# analog_in.net
KiCad netlist of a schematic drawn in Altium Designer
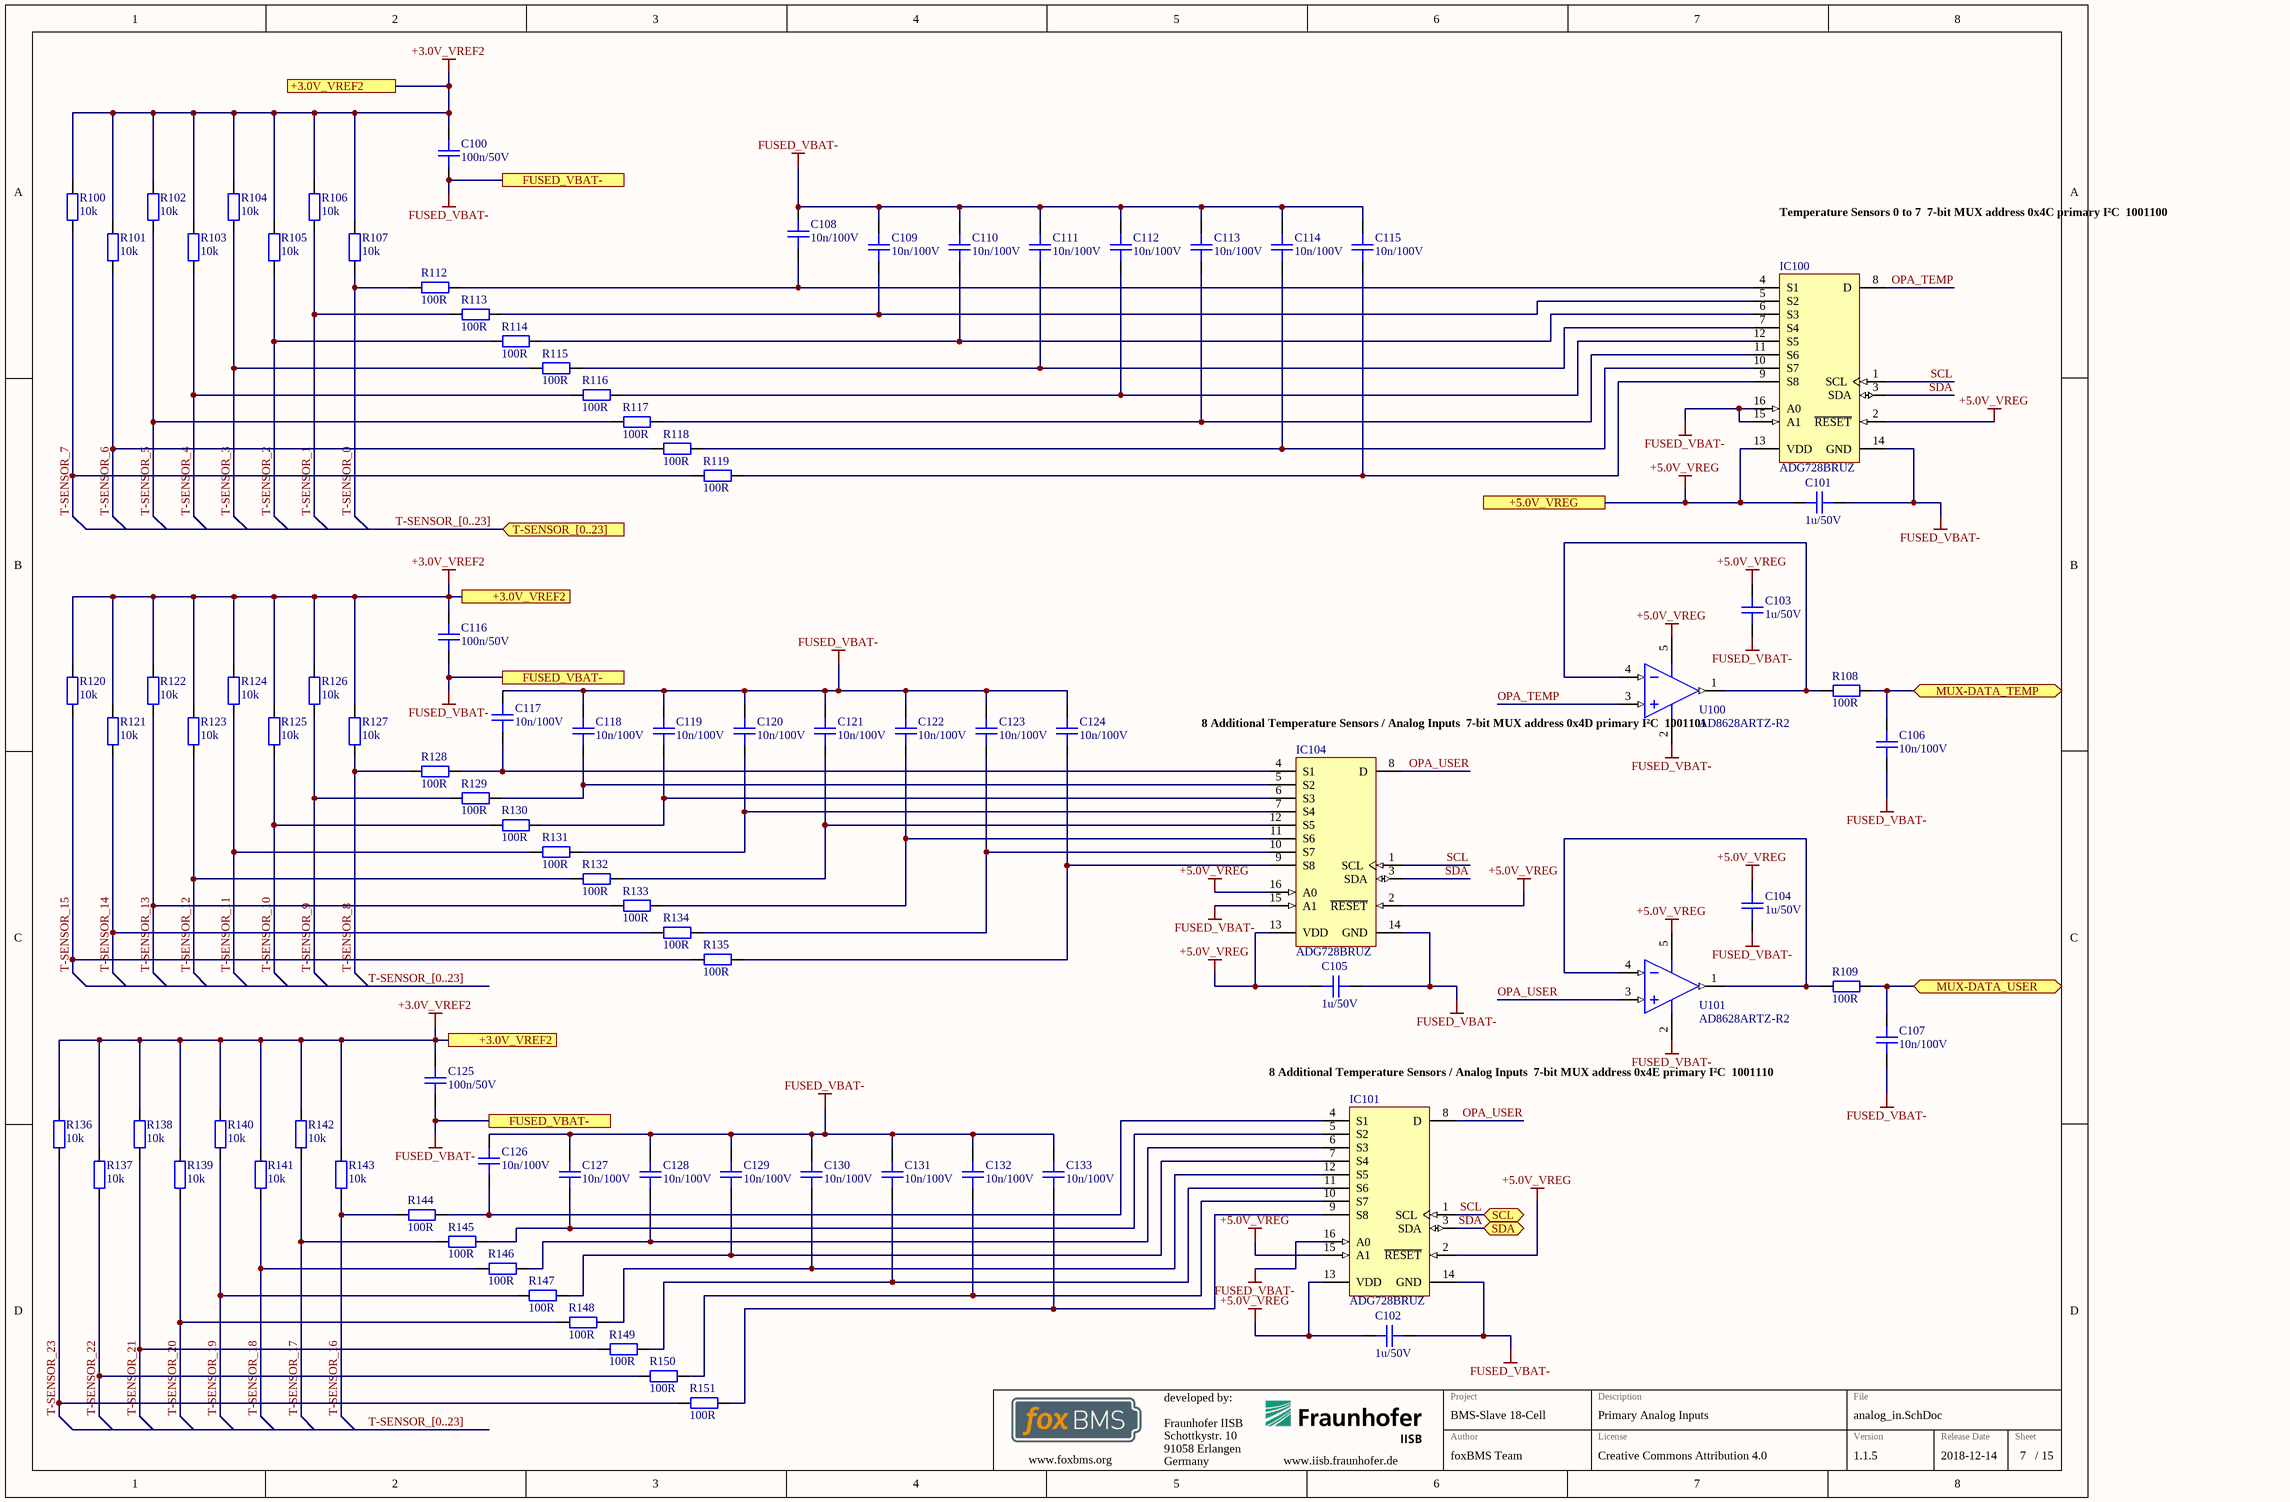
[diagram p0: analog_in.SchDoc]

(export (version "E")
  (design (tool "Eeschema 10.0.6"))
  (components
    (comp (ref "C100")
      (value "100n/50V")
      (footprint "CAPC1608X08N")
      (description "MLCC")
      (fields (field (name "PART NUMBER") "gen_C_ceramic_100n_50V_X7R_0603"))
      (libsource (lib "OE750") (part "C"))
    )
    (comp (ref "C101")
      (value "1u/50V")
      (footprint "CAPC2012X14N")
      (description "MLCC")
      (fields (field (name "PART NUMBER") "gen_C_ceramic_1u_50V_X7R_0805") (field (name "TOLERANCE") "± 10%"))
      (libsource (lib "OE750") (part "C"))
    )
    (comp (ref "C102")
      (value "1u/50V")
      (footprint "CAPC2012X14N")
      (description "MLCC")
      (fields (field (name "PART NUMBER") "gen_C_ceramic_1u_50V_X7R_0805") (field (name "TOLERANCE") "± 10%"))
      (libsource (lib "OE750") (part "C"))
    )
    (comp (ref "C103")
      (value "1u/50V")
      (footprint "CAPC2012X14N")
      (description "MLCC")
      (fields (field (name "PART NUMBER") "gen_C_ceramic_1u_50V_X7R_0805") (field (name "TOLERANCE") "± 10%"))
      (libsource (lib "OE750") (part "C"))
    )
    (comp (ref "C104")
      (value "1u/50V")
      (footprint "CAPC2012X14N")
      (description "MLCC")
      (fields (field (name "PART NUMBER") "gen_C_ceramic_1u_50V_X7R_0805") (field (name "TOLERANCE") "± 10%"))
      (libsource (lib "OE750") (part "C"))
    )
    (comp (ref "C105")
      (value "1u/50V")
      (footprint "CAPC2012X14N")
      (description "MLCC")
      (fields (field (name "PART NUMBER") "gen_C_ceramic_1u_50V_X7R_0805") (field (name "TOLERANCE") "± 10%"))
      (libsource (lib "OE750") (part "C"))
    )
    (comp (ref "C106")
      (value "10n/100V")
      (footprint "CAPC1608X08N")
      (description "MLCC")
      (fields (field (name "PART NUMBER") "gen_C_ceramic_10n_100V_X7R_0603"))
      (libsource (lib "OE750") (part "C"))
    )
    (comp (ref "C107")
      (value "10n/100V")
      (footprint "CAPC1608X08N")
      (description "MLCC")
      (fields (field (name "PART NUMBER") "gen_C_ceramic_10n_100V_X7R_0603"))
      (libsource (lib "OE750") (part "C"))
    )
    (comp (ref "C108")
      (value "10n/100V")
      (footprint "CAPC1608X08N")
      (description "MLCC")
      (fields (field (name "PART NUMBER") "gen_C_ceramic_10n_100V_X7R_0603"))
      (libsource (lib "OE750") (part "C"))
    )
    (comp (ref "C109")
      (value "10n/100V")
      (footprint "CAPC1608X08N")
      (description "MLCC")
      (fields (field (name "PART NUMBER") "gen_C_ceramic_10n_100V_X7R_0603"))
      (libsource (lib "OE750") (part "C"))
    )
    (comp (ref "C110")
      (value "10n/100V")
      (footprint "CAPC1608X08N")
      (description "MLCC")
      (fields (field (name "PART NUMBER") "gen_C_ceramic_10n_100V_X7R_0603"))
      (libsource (lib "OE750") (part "C"))
    )
    (comp (ref "C111")
      (value "10n/100V")
      (footprint "CAPC1608X08N")
      (description "MLCC")
      (fields (field (name "PART NUMBER") "gen_C_ceramic_10n_100V_X7R_0603"))
      (libsource (lib "OE750") (part "C"))
    )
    (comp (ref "C112")
      (value "10n/100V")
      (footprint "CAPC1608X08N")
      (description "MLCC")
      (fields (field (name "PART NUMBER") "gen_C_ceramic_10n_100V_X7R_0603"))
      (libsource (lib "OE750") (part "C"))
    )
    (comp (ref "C113")
      (value "10n/100V")
      (footprint "CAPC1608X08N")
      (description "MLCC")
      (fields (field (name "PART NUMBER") "gen_C_ceramic_10n_100V_X7R_0603"))
      (libsource (lib "OE750") (part "C"))
    )
    (comp (ref "C114")
      (value "10n/100V")
      (footprint "CAPC1608X08N")
      (description "MLCC")
      (fields (field (name "PART NUMBER") "gen_C_ceramic_10n_100V_X7R_0603"))
      (libsource (lib "OE750") (part "C"))
    )
    (comp (ref "C115")
      (value "10n/100V")
      (footprint "CAPC1608X08N")
      (description "MLCC")
      (fields (field (name "PART NUMBER") "gen_C_ceramic_10n_100V_X7R_0603"))
      (libsource (lib "OE750") (part "C"))
    )
    (comp (ref "C116")
      (value "100n/50V")
      (footprint "CAPC1608X08N")
      (description "MLCC")
      (fields (field (name "PART NUMBER") "gen_C_ceramic_100n_50V_X7R_0603"))
      (libsource (lib "OE750") (part "C"))
    )
    (comp (ref "C117")
      (value "10n/100V")
      (footprint "CAPC1608X08N")
      (description "MLCC")
      (fields (field (name "PART NUMBER") "gen_C_ceramic_10n_100V_X7R_0603"))
      (libsource (lib "OE750") (part "C"))
    )
    (comp (ref "C118")
      (value "10n/100V")
      (footprint "CAPC1608X08N")
      (description "MLCC")
      (fields (field (name "PART NUMBER") "gen_C_ceramic_10n_100V_X7R_0603"))
      (libsource (lib "OE750") (part "C"))
    )
    (comp (ref "C119")
      (value "10n/100V")
      (footprint "CAPC1608X08N")
      (description "MLCC")
      (fields (field (name "PART NUMBER") "gen_C_ceramic_10n_100V_X7R_0603"))
      (libsource (lib "OE750") (part "C"))
    )
    (comp (ref "C120")
      (value "10n/100V")
      (footprint "CAPC1608X08N")
      (description "MLCC")
      (fields (field (name "PART NUMBER") "gen_C_ceramic_10n_100V_X7R_0603"))
      (libsource (lib "OE750") (part "C"))
    )
    (comp (ref "C121")
      (value "10n/100V")
      (footprint "CAPC1608X08N")
      (description "MLCC")
      (fields (field (name "PART NUMBER") "gen_C_ceramic_10n_100V_X7R_0603"))
      (libsource (lib "OE750") (part "C"))
    )
    (comp (ref "C122")
      (value "10n/100V")
      (footprint "CAPC1608X08N")
      (description "MLCC")
      (fields (field (name "PART NUMBER") "gen_C_ceramic_10n_100V_X7R_0603"))
      (libsource (lib "OE750") (part "C"))
    )
    (comp (ref "C123")
      (value "10n/100V")
      (footprint "CAPC1608X08N")
      (description "MLCC")
      (fields (field (name "PART NUMBER") "gen_C_ceramic_10n_100V_X7R_0603"))
      (libsource (lib "OE750") (part "C"))
    )
    (comp (ref "C124")
      (value "10n/100V")
      (footprint "CAPC1608X08N")
      (description "MLCC")
      (fields (field (name "PART NUMBER") "gen_C_ceramic_10n_100V_X7R_0603"))
      (libsource (lib "OE750") (part "C"))
    )
    (comp (ref "C125")
      (value "100n/50V")
      (footprint "CAPC1608X08N")
      (description "MLCC")
      (fields (field (name "PART NUMBER") "gen_C_ceramic_100n_50V_X7R_0603"))
      (libsource (lib "OE750") (part "C"))
    )
    (comp (ref "C126")
      (value "10n/100V")
      (footprint "CAPC1608X08N")
      (description "MLCC")
      (fields (field (name "PART NUMBER") "gen_C_ceramic_10n_100V_X7R_0603"))
      (libsource (lib "OE750") (part "C"))
    )
    (comp (ref "C127")
      (value "10n/100V")
      (footprint "CAPC1608X08N")
      (description "MLCC")
      (fields (field (name "PART NUMBER") "gen_C_ceramic_10n_100V_X7R_0603"))
      (libsource (lib "OE750") (part "C"))
    )
    (comp (ref "C128")
      (value "10n/100V")
      (footprint "CAPC1608X08N")
      (description "MLCC")
      (fields (field (name "PART NUMBER") "gen_C_ceramic_10n_100V_X7R_0603"))
      (libsource (lib "OE750") (part "C"))
    )
    (comp (ref "C129")
      (value "10n/100V")
      (footprint "CAPC1608X08N")
      (description "MLCC")
      (fields (field (name "PART NUMBER") "gen_C_ceramic_10n_100V_X7R_0603"))
      (libsource (lib "OE750") (part "C"))
    )
    (comp (ref "C130")
      (value "10n/100V")
      (footprint "CAPC1608X08N")
      (description "MLCC")
      (fields (field (name "PART NUMBER") "gen_C_ceramic_10n_100V_X7R_0603"))
      (libsource (lib "OE750") (part "C"))
    )
    (comp (ref "C131")
      (value "10n/100V")
      (footprint "CAPC1608X08N")
      (description "MLCC")
      (fields (field (name "PART NUMBER") "gen_C_ceramic_10n_100V_X7R_0603"))
      (libsource (lib "OE750") (part "C"))
    )
    (comp (ref "C132")
      (value "10n/100V")
      (footprint "CAPC1608X08N")
      (description "MLCC")
      (fields (field (name "PART NUMBER") "gen_C_ceramic_10n_100V_X7R_0603"))
      (libsource (lib "OE750") (part "C"))
    )
    (comp (ref "C133")
      (value "10n/100V")
      (footprint "CAPC1608X08N")
      (description "MLCC")
      (fields (field (name "PART NUMBER") "gen_C_ceramic_10n_100V_X7R_0603"))
      (libsource (lib "OE750") (part "C"))
    )
    (comp (ref "IC100")
      (value "ADG728BRUZ")
      (footprint "ADI-RU-16_M")
      (fields (field (name "MANUFACTURER") "Analog Devices"))
      (libsource (lib "Altium Content Vault") (part "ADI-ADG728-RU-16"))
    )
    (comp (ref "IC101")
      (value "ADG728BRUZ")
      (footprint "ADI-RU-16_M")
      (fields (field (name "MANUFACTURER") "Analog Devices"))
      (libsource (lib "Altium Content Vault") (part "ADI-ADG728-RU-16"))
    )
    (comp (ref "IC104")
      (value "ADG728BRUZ")
      (footprint "ADI-RU-16_M")
      (fields (field (name "MANUFACTURER") "Analog Devices"))
      (libsource (lib "Altium Content Vault") (part "ADI-ADG728-RU-16"))
    )
    (comp (ref "R100")
      (value "10k")
      (footprint "RESC1608X05N")
      (description "SMD Resistor 10k 0603")
      (fields (field (name "PART NUMBER") "gen_R_10k_0603") (field (name "TOLERANCE") "1%"))
      (libsource (lib "OE750") (part "R"))
    )
    (comp (ref "R101")
      (value "10k")
      (footprint "RESC1608X05N")
      (description "SMD Resistor 10k 0603")
      (fields (field (name "PART NUMBER") "gen_R_10k_0603") (field (name "TOLERANCE") "1%"))
      (libsource (lib "OE750") (part "R"))
    )
    (comp (ref "R102")
      (value "10k")
      (footprint "RESC1608X05N")
      (description "SMD Resistor 10k 0603")
      (fields (field (name "PART NUMBER") "gen_R_10k_0603") (field (name "TOLERANCE") "1%"))
      (libsource (lib "OE750") (part "R"))
    )
    (comp (ref "R103")
      (value "10k")
      (footprint "RESC1608X05N")
      (description "SMD Resistor 10k 0603")
      (fields (field (name "PART NUMBER") "gen_R_10k_0603") (field (name "TOLERANCE") "1%"))
      (libsource (lib "OE750") (part "R"))
    )
    (comp (ref "R104")
      (value "10k")
      (footprint "RESC1608X05N")
      (description "SMD Resistor 10k 0603")
      (fields (field (name "PART NUMBER") "gen_R_10k_0603") (field (name "TOLERANCE") "1%"))
      (libsource (lib "OE750") (part "R"))
    )
    (comp (ref "R105")
      (value "10k")
      (footprint "RESC1608X05N")
      (description "SMD Resistor 10k 0603")
      (fields (field (name "PART NUMBER") "gen_R_10k_0603") (field (name "TOLERANCE") "1%"))
      (libsource (lib "OE750") (part "R"))
    )
    (comp (ref "R106")
      (value "10k")
      (footprint "RESC1608X05N")
      (description "SMD Resistor 10k 0603")
      (fields (field (name "PART NUMBER") "gen_R_10k_0603") (field (name "TOLERANCE") "1%"))
      (libsource (lib "OE750") (part "R"))
    )
    (comp (ref "R107")
      (value "10k")
      (footprint "RESC1608X05N")
      (description "SMD Resistor 10k 0603")
      (fields (field (name "PART NUMBER") "gen_R_10k_0603") (field (name "TOLERANCE") "1%"))
      (libsource (lib "OE750") (part "R"))
    )
    (comp (ref "R108")
      (value "100R")
      (footprint "RESC1608X05N")
      (description "SMD Resistor 100R 0603")
      (fields (field (name "PART NUMBER") "gen_R_100R_0603") (field (name "TOLERANCE") "1%"))
      (libsource (lib "OE750") (part "R"))
    )
    (comp (ref "R109")
      (value "100R")
      (footprint "RESC1608X05N")
      (description "SMD Resistor 100R 0603")
      (fields (field (name "PART NUMBER") "gen_R_100R_0603") (field (name "TOLERANCE") "1%"))
      (libsource (lib "OE750") (part "R"))
    )
    (comp (ref "R112")
      (value "100R")
      (footprint "RESC1608X05N")
      (description "SMD Resistor 100R 0603")
      (fields (field (name "PART NUMBER") "gen_R_100R_0603") (field (name "TOLERANCE") "1%"))
      (libsource (lib "OE750") (part "R"))
    )
    (comp (ref "R113")
      (value "100R")
      (footprint "RESC1608X05N")
      (description "SMD Resistor 100R 0603")
      (fields (field (name "PART NUMBER") "gen_R_100R_0603") (field (name "TOLERANCE") "1%"))
      (libsource (lib "OE750") (part "R"))
    )
    (comp (ref "R114")
      (value "100R")
      (footprint "RESC1608X05N")
      (description "SMD Resistor 100R 0603")
      (fields (field (name "PART NUMBER") "gen_R_100R_0603") (field (name "TOLERANCE") "1%"))
      (libsource (lib "OE750") (part "R"))
    )
    (comp (ref "R115")
      (value "100R")
      (footprint "RESC1608X05N")
      (description "SMD Resistor 100R 0603")
      (fields (field (name "PART NUMBER") "gen_R_100R_0603") (field (name "TOLERANCE") "1%"))
      (libsource (lib "OE750") (part "R"))
    )
    (comp (ref "R116")
      (value "100R")
      (footprint "RESC1608X05N")
      (description "SMD Resistor 100R 0603")
      (fields (field (name "PART NUMBER") "gen_R_100R_0603") (field (name "TOLERANCE") "1%"))
      (libsource (lib "OE750") (part "R"))
    )
    (comp (ref "R117")
      (value "100R")
      (footprint "RESC1608X05N")
      (description "SMD Resistor 100R 0603")
      (fields (field (name "PART NUMBER") "gen_R_100R_0603") (field (name "TOLERANCE") "1%"))
      (libsource (lib "OE750") (part "R"))
    )
    (comp (ref "R118")
      (value "100R")
      (footprint "RESC1608X05N")
      (description "SMD Resistor 100R 0603")
      (fields (field (name "PART NUMBER") "gen_R_100R_0603") (field (name "TOLERANCE") "1%"))
      (libsource (lib "OE750") (part "R"))
    )
    (comp (ref "R119")
      (value "100R")
      (footprint "RESC1608X05N")
      (description "SMD Resistor 100R 0603")
      (fields (field (name "PART NUMBER") "gen_R_100R_0603") (field (name "TOLERANCE") "1%"))
      (libsource (lib "OE750") (part "R"))
    )
    (comp (ref "R120")
      (value "10k")
      (footprint "RESC1608X05N")
      (description "SMD Resistor 10k 0603")
      (fields (field (name "PART NUMBER") "gen_R_10k_0603") (field (name "TOLERANCE") "1%"))
      (libsource (lib "OE750") (part "R"))
    )
    (comp (ref "R121")
      (value "10k")
      (footprint "RESC1608X05N")
      (description "SMD Resistor 10k 0603")
      (fields (field (name "PART NUMBER") "gen_R_10k_0603") (field (name "TOLERANCE") "1%"))
      (libsource (lib "OE750") (part "R"))
    )
    (comp (ref "R122")
      (value "10k")
      (footprint "RESC1608X05N")
      (description "SMD Resistor 10k 0603")
      (fields (field (name "PART NUMBER") "gen_R_10k_0603") (field (name "TOLERANCE") "1%"))
      (libsource (lib "OE750") (part "R"))
    )
    (comp (ref "R123")
      (value "10k")
      (footprint "RESC1608X05N")
      (description "SMD Resistor 10k 0603")
      (fields (field (name "PART NUMBER") "gen_R_10k_0603") (field (name "TOLERANCE") "1%"))
      (libsource (lib "OE750") (part "R"))
    )
    (comp (ref "R124")
      (value "10k")
      (footprint "RESC1608X05N")
      (description "SMD Resistor 10k 0603")
      (fields (field (name "PART NUMBER") "gen_R_10k_0603") (field (name "TOLERANCE") "1%"))
      (libsource (lib "OE750") (part "R"))
    )
    (comp (ref "R125")
      (value "10k")
      (footprint "RESC1608X05N")
      (description "SMD Resistor 10k 0603")
      (fields (field (name "PART NUMBER") "gen_R_10k_0603") (field (name "TOLERANCE") "1%"))
      (libsource (lib "OE750") (part "R"))
    )
    (comp (ref "R126")
      (value "10k")
      (footprint "RESC1608X05N")
      (description "SMD Resistor 10k 0603")
      (fields (field (name "PART NUMBER") "gen_R_10k_0603") (field (name "TOLERANCE") "1%"))
      (libsource (lib "OE750") (part "R"))
    )
    (comp (ref "R127")
      (value "10k")
      (footprint "RESC1608X05N")
      (description "SMD Resistor 10k 0603")
      (fields (field (name "PART NUMBER") "gen_R_10k_0603") (field (name "TOLERANCE") "1%"))
      (libsource (lib "OE750") (part "R"))
    )
    (comp (ref "R128")
      (value "100R")
      (footprint "RESC1608X05N")
      (description "SMD Resistor 100R 0603")
      (fields (field (name "PART NUMBER") "gen_R_100R_0603") (field (name "TOLERANCE") "1%"))
      (libsource (lib "OE750") (part "R"))
    )
    (comp (ref "R129")
      (value "100R")
      (footprint "RESC1608X05N")
      (description "SMD Resistor 100R 0603")
      (fields (field (name "PART NUMBER") "gen_R_100R_0603") (field (name "TOLERANCE") "1%"))
      (libsource (lib "OE750") (part "R"))
    )
    (comp (ref "R130")
      (value "100R")
      (footprint "RESC1608X05N")
      (description "SMD Resistor 100R 0603")
      (fields (field (name "PART NUMBER") "gen_R_100R_0603") (field (name "TOLERANCE") "1%"))
      (libsource (lib "OE750") (part "R"))
    )
    (comp (ref "R131")
      (value "100R")
      (footprint "RESC1608X05N")
      (description "SMD Resistor 100R 0603")
      (fields (field (name "PART NUMBER") "gen_R_100R_0603") (field (name "TOLERANCE") "1%"))
      (libsource (lib "OE750") (part "R"))
    )
    (comp (ref "R132")
      (value "100R")
      (footprint "RESC1608X05N")
      (description "SMD Resistor 100R 0603")
      (fields (field (name "PART NUMBER") "gen_R_100R_0603") (field (name "TOLERANCE") "1%"))
      (libsource (lib "OE750") (part "R"))
    )
    (comp (ref "R133")
      (value "100R")
      (footprint "RESC1608X05N")
      (description "SMD Resistor 100R 0603")
      (fields (field (name "PART NUMBER") "gen_R_100R_0603") (field (name "TOLERANCE") "1%"))
      (libsource (lib "OE750") (part "R"))
    )
    (comp (ref "R134")
      (value "100R")
      (footprint "RESC1608X05N")
      (description "SMD Resistor 100R 0603")
      (fields (field (name "PART NUMBER") "gen_R_100R_0603") (field (name "TOLERANCE") "1%"))
      (libsource (lib "OE750") (part "R"))
    )
    (comp (ref "R135")
      (value "100R")
      (footprint "RESC1608X05N")
      (description "SMD Resistor 100R 0603")
      (fields (field (name "PART NUMBER") "gen_R_100R_0603") (field (name "TOLERANCE") "1%"))
      (libsource (lib "OE750") (part "R"))
    )
    (comp (ref "R136")
      (value "10k")
      (footprint "RESC1608X05N")
      (description "SMD Resistor 10k 0603")
      (fields (field (name "PART NUMBER") "gen_R_10k_0603") (field (name "TOLERANCE") "1%"))
      (libsource (lib "OE750") (part "R"))
    )
    (comp (ref "R137")
      (value "10k")
      (footprint "RESC1608X05N")
      (description "SMD Resistor 10k 0603")
      (fields (field (name "PART NUMBER") "gen_R_10k_0603") (field (name "TOLERANCE") "1%"))
      (libsource (lib "OE750") (part "R"))
    )
    (comp (ref "R138")
      (value "10k")
      (footprint "RESC1608X05N")
      (description "SMD Resistor 10k 0603")
      (fields (field (name "PART NUMBER") "gen_R_10k_0603") (field (name "TOLERANCE") "1%"))
      (libsource (lib "OE750") (part "R"))
    )
    (comp (ref "R139")
      (value "10k")
      (footprint "RESC1608X05N")
      (description "SMD Resistor 10k 0603")
      (fields (field (name "PART NUMBER") "gen_R_10k_0603") (field (name "TOLERANCE") "1%"))
      (libsource (lib "OE750") (part "R"))
    )
    (comp (ref "R140")
      (value "10k")
      (footprint "RESC1608X05N")
      (description "SMD Resistor 10k 0603")
      (fields (field (name "PART NUMBER") "gen_R_10k_0603") (field (name "TOLERANCE") "1%"))
      (libsource (lib "OE750") (part "R"))
    )
    (comp (ref "R141")
      (value "10k")
      (footprint "RESC1608X05N")
      (description "SMD Resistor 10k 0603")
      (fields (field (name "PART NUMBER") "gen_R_10k_0603") (field (name "TOLERANCE") "1%"))
      (libsource (lib "OE750") (part "R"))
    )
    (comp (ref "R142")
      (value "10k")
      (footprint "RESC1608X05N")
      (description "SMD Resistor 10k 0603")
      (fields (field (name "PART NUMBER") "gen_R_10k_0603") (field (name "TOLERANCE") "1%"))
      (libsource (lib "OE750") (part "R"))
    )
    (comp (ref "R143")
      (value "10k")
      (footprint "RESC1608X05N")
      (description "SMD Resistor 10k 0603")
      (fields (field (name "PART NUMBER") "gen_R_10k_0603") (field (name "TOLERANCE") "1%"))
      (libsource (lib "OE750") (part "R"))
    )
    (comp (ref "R144")
      (value "100R")
      (footprint "RESC1608X05N")
      (description "SMD Resistor 100R 0603")
      (fields (field (name "PART NUMBER") "gen_R_100R_0603") (field (name "TOLERANCE") "1%"))
      (libsource (lib "OE750") (part "R"))
    )
    (comp (ref "R145")
      (value "100R")
      (footprint "RESC1608X05N")
      (description "SMD Resistor 100R 0603")
      (fields (field (name "PART NUMBER") "gen_R_100R_0603") (field (name "TOLERANCE") "1%"))
      (libsource (lib "OE750") (part "R"))
    )
    (comp (ref "R146")
      (value "100R")
      (footprint "RESC1608X05N")
      (description "SMD Resistor 100R 0603")
      (fields (field (name "PART NUMBER") "gen_R_100R_0603") (field (name "TOLERANCE") "1%"))
      (libsource (lib "OE750") (part "R"))
    )
    (comp (ref "R147")
      (value "100R")
      (footprint "RESC1608X05N")
      (description "SMD Resistor 100R 0603")
      (fields (field (name "PART NUMBER") "gen_R_100R_0603") (field (name "TOLERANCE") "1%"))
      (libsource (lib "OE750") (part "R"))
    )
    (comp (ref "R148")
      (value "100R")
      (footprint "RESC1608X05N")
      (description "SMD Resistor 100R 0603")
      (fields (field (name "PART NUMBER") "gen_R_100R_0603") (field (name "TOLERANCE") "1%"))
      (libsource (lib "OE750") (part "R"))
    )
    (comp (ref "R149")
      (value "100R")
      (footprint "RESC1608X05N")
      (description "SMD Resistor 100R 0603")
      (fields (field (name "PART NUMBER") "gen_R_100R_0603") (field (name "TOLERANCE") "1%"))
      (libsource (lib "OE750") (part "R"))
    )
    (comp (ref "R150")
      (value "100R")
      (footprint "RESC1608X05N")
      (description "SMD Resistor 100R 0603")
      (fields (field (name "PART NUMBER") "gen_R_100R_0603") (field (name "TOLERANCE") "1%"))
      (libsource (lib "OE750") (part "R"))
    )
    (comp (ref "R151")
      (value "100R")
      (footprint "RESC1608X05N")
      (description "SMD Resistor 100R 0603")
      (fields (field (name "PART NUMBER") "gen_R_100R_0603") (field (name "TOLERANCE") "1%"))
      (libsource (lib "OE750") (part "R"))
    )
    (comp (ref "U100")
      (value "AD8628ARTZ-R2")
      (footprint "ADI-RJ-5_M")
      (fields (field (name "MANUFACTURER") "Analog Devices") (field (name "GENERIC PART NUMBER") "AD8628"))
      (libsource (lib "Altium Content Vault") (part "ADI-ADxxxx-X-5"))
    )
    (comp (ref "U101")
      (value "AD8628ARTZ-R2")
      (footprint "ADI-RJ-5_M")
      (fields (field (name "MANUFACTURER") "Analog Devices") (field (name "GENERIC PART NUMBER") "AD8628"))
      (libsource (lib "Altium Content Vault") (part "ADI-ADxxxx-X-5"))
    )
  )
  (nets
    (net (code "1") (name "+3.0V_VREF2") (class "Default")
      (node (ref "C100") (pin "2") (pinfunction "2_2") (pintype "passive"))
      (node (ref "C116") (pin "2") (pinfunction "2_2") (pintype "passive"))
      (node (ref "C125") (pin "2") (pinfunction "2_2") (pintype "passive"))
      (node (ref "R100") (pin "2") (pinfunction "2_2") (pintype "passive"))
      (node (ref "R101") (pin "2") (pinfunction "2_2") (pintype "passive"))
      (node (ref "R102") (pin "2") (pinfunction "2_2") (pintype "passive"))
      (node (ref "R103") (pin "2") (pinfunction "2_2") (pintype "passive"))
      (node (ref "R104") (pin "2") (pinfunction "2_2") (pintype "passive"))
      (node (ref "R105") (pin "2") (pinfunction "2_2") (pintype "passive"))
      (node (ref "R106") (pin "2") (pinfunction "2_2") (pintype "passive"))
      (node (ref "R107") (pin "2") (pinfunction "2_2") (pintype "passive"))
      (node (ref "R120") (pin "2") (pinfunction "2_2") (pintype "passive"))
      (node (ref "R121") (pin "2") (pinfunction "2_2") (pintype "passive"))
      (node (ref "R122") (pin "2") (pinfunction "2_2") (pintype "passive"))
      (node (ref "R123") (pin "2") (pinfunction "2_2") (pintype "passive"))
      (node (ref "R124") (pin "2") (pinfunction "2_2") (pintype "passive"))
      (node (ref "R125") (pin "2") (pinfunction "2_2") (pintype "passive"))
      (node (ref "R126") (pin "2") (pinfunction "2_2") (pintype "passive"))
      (node (ref "R127") (pin "2") (pinfunction "2_2") (pintype "passive"))
      (node (ref "R136") (pin "2") (pinfunction "2_2") (pintype "passive"))
      (node (ref "R137") (pin "2") (pinfunction "2_2") (pintype "passive"))
      (node (ref "R138") (pin "2") (pinfunction "2_2") (pintype "passive"))
      (node (ref "R139") (pin "2") (pinfunction "2_2") (pintype "passive"))
      (node (ref "R140") (pin "2") (pinfunction "2_2") (pintype "passive"))
      (node (ref "R141") (pin "2") (pinfunction "2_2") (pintype "passive"))
      (node (ref "R142") (pin "2") (pinfunction "2_2") (pintype "passive"))
      (node (ref "R143") (pin "2") (pinfunction "2_2") (pintype "passive"))
    )
    (net (code "2") (name "+5.0V_VREG") (class "Default")
      (node (ref "C101") (pin "2") (pinfunction "2_2") (pintype "passive"))
      (node (ref "C102") (pin "2") (pinfunction "2_2") (pintype "passive"))
      (node (ref "C103") (pin "2") (pinfunction "2_2") (pintype "passive"))
      (node (ref "C104") (pin "2") (pinfunction "2_2") (pintype "passive"))
      (node (ref "C105") (pin "2") (pinfunction "2_2") (pintype "passive"))
      (node (ref "IC100") (pin "13") (pinfunction "VDD_13") (pintype "power_in"))
      (node (ref "IC100") (pin "2") (pinfunction "~{RESET}_2") (pintype "input"))
      (node (ref "IC101") (pin "13") (pinfunction "VDD_13") (pintype "power_in"))
      (node (ref "IC101") (pin "15") (pinfunction "A1_15") (pintype "input"))
      (node (ref "IC101") (pin "2") (pinfunction "~{RESET}_2") (pintype "input"))
      (node (ref "IC104") (pin "13") (pinfunction "VDD_13") (pintype "power_in"))
      (node (ref "IC104") (pin "16") (pinfunction "A0_16") (pintype "input"))
      (node (ref "IC104") (pin "2") (pinfunction "~{RESET}_2") (pintype "input"))
      (node (ref "U100") (pin "5") (pinfunction "+V_5") (pintype "power_in"))
      (node (ref "U101") (pin "5") (pinfunction "+V_5") (pintype "power_in"))
    )
    (net (code "3") (name "/MUX-DATA_TEMP") (class "Default")
      (node (ref "C106") (pin "2") (pinfunction "2_2") (pintype "passive"))
      (node (ref "R108") (pin "2") (pinfunction "2_2") (pintype "passive"))
    )
    (net (code "4") (name "/MUX-DATA_USER") (class "Default")
      (node (ref "C107") (pin "2") (pinfunction "2_2") (pintype "passive"))
      (node (ref "R109") (pin "2") (pinfunction "2_2") (pintype "passive"))
    )
    (net (code "5") (name "/OPA_TEMP") (class "Default")
      (node (ref "IC100") (pin "8") (pinfunction "D_8") (pintype "passive"))
      (node (ref "U100") (pin "3") (pinfunction "+IN_3") (pintype "input"))
    )
    (net (code "6") (name "/OPA_USER") (class "Default")
      (node (ref "IC101") (pin "8") (pinfunction "D_8") (pintype "passive"))
      (node (ref "IC104") (pin "8") (pinfunction "D_8") (pintype "passive"))
      (node (ref "U101") (pin "3") (pinfunction "+IN_3") (pintype "input"))
    )
    (net (code "7") (name "/SCL") (class "Default")
      (node (ref "IC100") (pin "1") (pinfunction "SCL_1") (pintype "input"))
      (node (ref "IC101") (pin "1") (pinfunction "SCL_1") (pintype "input"))
      (node (ref "IC104") (pin "1") (pinfunction "SCL_1") (pintype "input"))
    )
    (net (code "8") (name "/SDA") (class "Default")
      (node (ref "IC100") (pin "3") (pinfunction "SDA_3") (pintype "bidirectional"))
      (node (ref "IC101") (pin "3") (pinfunction "SDA_3") (pintype "bidirectional"))
      (node (ref "IC104") (pin "3") (pinfunction "SDA_3") (pintype "bidirectional"))
    )
    (net (code "9") (name "/T-SENSOR_0") (class "Default")
      (node (ref "R107") (pin "1") (pinfunction "1_1") (pintype "passive"))
      (node (ref "R112") (pin "2") (pinfunction "2_2") (pintype "passive"))
    )
    (net (code "10") (name "/T-SENSOR_1") (class "Default")
      (node (ref "R106") (pin "1") (pinfunction "1_1") (pintype "passive"))
      (node (ref "R113") (pin "2") (pinfunction "2_2") (pintype "passive"))
    )
    (net (code "11") (name "/T-SENSOR_2") (class "Default")
      (node (ref "R105") (pin "1") (pinfunction "1_1") (pintype "passive"))
      (node (ref "R114") (pin "2") (pinfunction "2_2") (pintype "passive"))
    )
    (net (code "12") (name "/T-SENSOR_3") (class "Default")
      (node (ref "R104") (pin "1") (pinfunction "1_1") (pintype "passive"))
      (node (ref "R115") (pin "2") (pinfunction "2_2") (pintype "passive"))
    )
    (net (code "13") (name "/T-SENSOR_4") (class "Default")
      (node (ref "R103") (pin "1") (pinfunction "1_1") (pintype "passive"))
      (node (ref "R116") (pin "2") (pinfunction "2_2") (pintype "passive"))
    )
    (net (code "14") (name "/T-SENSOR_5") (class "Default")
      (node (ref "R102") (pin "1") (pinfunction "1_1") (pintype "passive"))
      (node (ref "R117") (pin "2") (pinfunction "2_2") (pintype "passive"))
    )
    (net (code "15") (name "/T-SENSOR_6") (class "Default")
      (node (ref "R101") (pin "1") (pinfunction "1_1") (pintype "passive"))
      (node (ref "R118") (pin "2") (pinfunction "2_2") (pintype "passive"))
    )
    (net (code "16") (name "/T-SENSOR_7") (class "Default")
      (node (ref "R100") (pin "1") (pinfunction "1_1") (pintype "passive"))
      (node (ref "R119") (pin "2") (pinfunction "2_2") (pintype "passive"))
    )
    (net (code "17") (name "/T-SENSOR_8") (class "Default")
      (node (ref "R127") (pin "1") (pinfunction "1_1") (pintype "passive"))
      (node (ref "R128") (pin "2") (pinfunction "2_2") (pintype "passive"))
    )
    (net (code "18") (name "/T-SENSOR_9") (class "Default")
      (node (ref "R126") (pin "1") (pinfunction "1_1") (pintype "passive"))
      (node (ref "R129") (pin "2") (pinfunction "2_2") (pintype "passive"))
    )
    (net (code "19") (name "/T-SENSOR_10") (class "Default")
      (node (ref "R125") (pin "1") (pinfunction "1_1") (pintype "passive"))
      (node (ref "R130") (pin "2") (pinfunction "2_2") (pintype "passive"))
    )
    (net (code "20") (name "/T-SENSOR_11") (class "Default")
      (node (ref "R124") (pin "1") (pinfunction "1_1") (pintype "passive"))
      (node (ref "R131") (pin "2") (pinfunction "2_2") (pintype "passive"))
    )
    (net (code "21") (name "/T-SENSOR_12") (class "Default")
      (node (ref "R123") (pin "1") (pinfunction "1_1") (pintype "passive"))
      (node (ref "R132") (pin "2") (pinfunction "2_2") (pintype "passive"))
    )
    (net (code "22") (name "/T-SENSOR_13") (class "Default")
      (node (ref "R122") (pin "1") (pinfunction "1_1") (pintype "passive"))
      (node (ref "R133") (pin "2") (pinfunction "2_2") (pintype "passive"))
    )
    (net (code "23") (name "/T-SENSOR_14") (class "Default")
      (node (ref "R121") (pin "1") (pinfunction "1_1") (pintype "passive"))
      (node (ref "R134") (pin "2") (pinfunction "2_2") (pintype "passive"))
    )
    (net (code "24") (name "/T-SENSOR_15") (class "Default")
      (node (ref "R120") (pin "1") (pinfunction "1_1") (pintype "passive"))
      (node (ref "R135") (pin "2") (pinfunction "2_2") (pintype "passive"))
    )
    (net (code "25") (name "/T-SENSOR_16") (class "Default")
      (node (ref "R143") (pin "1") (pinfunction "1_1") (pintype "passive"))
      (node (ref "R144") (pin "2") (pinfunction "2_2") (pintype "passive"))
    )
    (net (code "26") (name "/T-SENSOR_17") (class "Default")
      (node (ref "R142") (pin "1") (pinfunction "1_1") (pintype "passive"))
      (node (ref "R145") (pin "2") (pinfunction "2_2") (pintype "passive"))
    )
    (net (code "27") (name "/T-SENSOR_18") (class "Default")
      (node (ref "R141") (pin "1") (pinfunction "1_1") (pintype "passive"))
      (node (ref "R146") (pin "2") (pinfunction "2_2") (pintype "passive"))
    )
    (net (code "28") (name "/T-SENSOR_19") (class "Default")
      (node (ref "R140") (pin "1") (pinfunction "1_1") (pintype "passive"))
      (node (ref "R147") (pin "2") (pinfunction "2_2") (pintype "passive"))
    )
    (net (code "29") (name "/T-SENSOR_20") (class "Default")
      (node (ref "R139") (pin "1") (pinfunction "1_1") (pintype "passive"))
      (node (ref "R148") (pin "2") (pinfunction "2_2") (pintype "passive"))
    )
    (net (code "30") (name "/T-SENSOR_21") (class "Default")
      (node (ref "R138") (pin "1") (pinfunction "1_1") (pintype "passive"))
      (node (ref "R149") (pin "2") (pinfunction "2_2") (pintype "passive"))
    )
    (net (code "31") (name "/T-SENSOR_22") (class "Default")
      (node (ref "R137") (pin "1") (pinfunction "1_1") (pintype "passive"))
      (node (ref "R150") (pin "2") (pinfunction "2_2") (pintype "passive"))
    )
    (net (code "32") (name "/T-SENSOR_23") (class "Default")
      (node (ref "R136") (pin "1") (pinfunction "1_1") (pintype "passive"))
      (node (ref "R151") (pin "2") (pinfunction "2_2") (pintype "passive"))
    )
    (net (code "34") (name "FUSED_VBAT-") (class "Default")
      (node (ref "C100") (pin "1") (pinfunction "1_1") (pintype "passive"))
      (node (ref "C101") (pin "1") (pinfunction "1_1") (pintype "passive"))
      (node (ref "C102") (pin "1") (pinfunction "1_1") (pintype "passive"))
      (node (ref "C103") (pin "1") (pinfunction "1_1") (pintype "passive"))
      (node (ref "C104") (pin "1") (pinfunction "1_1") (pintype "passive"))
      (node (ref "C105") (pin "1") (pinfunction "1_1") (pintype "passive"))
      (node (ref "C106") (pin "1") (pinfunction "1_1") (pintype "passive"))
      (node (ref "C107") (pin "1") (pinfunction "1_1") (pintype "passive"))
      (node (ref "C108") (pin "1") (pinfunction "1_1") (pintype "passive"))
      (node (ref "C109") (pin "1") (pinfunction "1_1") (pintype "passive"))
      (node (ref "C110") (pin "1") (pinfunction "1_1") (pintype "passive"))
      (node (ref "C111") (pin "1") (pinfunction "1_1") (pintype "passive"))
      (node (ref "C112") (pin "1") (pinfunction "1_1") (pintype "passive"))
      (node (ref "C113") (pin "1") (pinfunction "1_1") (pintype "passive"))
      (node (ref "C114") (pin "1") (pinfunction "1_1") (pintype "passive"))
      (node (ref "C115") (pin "1") (pinfunction "1_1") (pintype "passive"))
      (node (ref "C116") (pin "1") (pinfunction "1_1") (pintype "passive"))
      (node (ref "C117") (pin "1") (pinfunction "1_1") (pintype "passive"))
      (node (ref "C118") (pin "1") (pinfunction "1_1") (pintype "passive"))
      (node (ref "C119") (pin "1") (pinfunction "1_1") (pintype "passive"))
      (node (ref "C120") (pin "1") (pinfunction "1_1") (pintype "passive"))
      (node (ref "C121") (pin "1") (pinfunction "1_1") (pintype "passive"))
      (node (ref "C122") (pin "1") (pinfunction "1_1") (pintype "passive"))
      (node (ref "C123") (pin "1") (pinfunction "1_1") (pintype "passive"))
      (node (ref "C124") (pin "1") (pinfunction "1_1") (pintype "passive"))
      (node (ref "C125") (pin "1") (pinfunction "1_1") (pintype "passive"))
      (node (ref "C126") (pin "1") (pinfunction "1_1") (pintype "passive"))
      (node (ref "C127") (pin "1") (pinfunction "1_1") (pintype "passive"))
      (node (ref "C128") (pin "1") (pinfunction "1_1") (pintype "passive"))
      (node (ref "C129") (pin "1") (pinfunction "1_1") (pintype "passive"))
      (node (ref "C130") (pin "1") (pinfunction "1_1") (pintype "passive"))
      (node (ref "C131") (pin "1") (pinfunction "1_1") (pintype "passive"))
      (node (ref "C132") (pin "1") (pinfunction "1_1") (pintype "passive"))
      (node (ref "C133") (pin "1") (pinfunction "1_1") (pintype "passive"))
      (node (ref "IC100") (pin "14") (pinfunction "GND_14") (pintype "power_in"))
      (node (ref "IC100") (pin "15") (pinfunction "A1_15") (pintype "input"))
      (node (ref "IC100") (pin "16") (pinfunction "A0_16") (pintype "input"))
      (node (ref "IC101") (pin "14") (pinfunction "GND_14") (pintype "power_in"))
      (node (ref "IC101") (pin "16") (pinfunction "A0_16") (pintype "input"))
      (node (ref "IC104") (pin "14") (pinfunction "GND_14") (pintype "power_in"))
      (node (ref "IC104") (pin "15") (pinfunction "A1_15") (pintype "input"))
      (node (ref "U100") (pin "2") (pinfunction "-V_2") (pintype "power_in"))
      (node (ref "U101") (pin "2") (pinfunction "-V_2") (pintype "power_in"))
    )
    (net (code "35") (name "Net-(IC100-S1)") (class "Default")
      (node (ref "C108") (pin "2") (pinfunction "2_2") (pintype "passive"))
      (node (ref "IC100") (pin "4") (pinfunction "S1_4") (pintype "passive"))
      (node (ref "R112") (pin "1") (pinfunction "1_1") (pintype "passive"))
    )
    (net (code "36") (name "Net-(IC100-S2)") (class "Default")
      (node (ref "C109") (pin "2") (pinfunction "2_2") (pintype "passive"))
      (node (ref "IC100") (pin "5") (pinfunction "S2_5") (pintype "passive"))
      (node (ref "R113") (pin "1") (pinfunction "1_1") (pintype "passive"))
    )
    (net (code "37") (name "Net-(IC100-S3)") (class "Default")
      (node (ref "C110") (pin "2") (pinfunction "2_2") (pintype "passive"))
      (node (ref "IC100") (pin "6") (pinfunction "S3_6") (pintype "passive"))
      (node (ref "R114") (pin "1") (pinfunction "1_1") (pintype "passive"))
    )
    (net (code "38") (name "Net-(IC100-S4)") (class "Default")
      (node (ref "C111") (pin "2") (pinfunction "2_2") (pintype "passive"))
      (node (ref "IC100") (pin "7") (pinfunction "S4_7") (pintype "passive"))
      (node (ref "R115") (pin "1") (pinfunction "1_1") (pintype "passive"))
    )
    (net (code "39") (name "Net-(IC100-S5)") (class "Default")
      (node (ref "C112") (pin "2") (pinfunction "2_2") (pintype "passive"))
      (node (ref "IC100") (pin "12") (pinfunction "S5_12") (pintype "passive"))
      (node (ref "R116") (pin "1") (pinfunction "1_1") (pintype "passive"))
    )
    (net (code "40") (name "Net-(IC100-S6)") (class "Default")
      (node (ref "C113") (pin "2") (pinfunction "2_2") (pintype "passive"))
      (node (ref "IC100") (pin "11") (pinfunction "S6_11") (pintype "passive"))
      (node (ref "R117") (pin "1") (pinfunction "1_1") (pintype "passive"))
    )
    (net (code "41") (name "Net-(IC100-S7)") (class "Default")
      (node (ref "C114") (pin "2") (pinfunction "2_2") (pintype "passive"))
      (node (ref "IC100") (pin "10") (pinfunction "S7_10") (pintype "passive"))
      (node (ref "R118") (pin "1") (pinfunction "1_1") (pintype "passive"))
    )
    (net (code "42") (name "Net-(IC100-S8)") (class "Default")
      (node (ref "C115") (pin "2") (pinfunction "2_2") (pintype "passive"))
      (node (ref "IC100") (pin "9") (pinfunction "S8_9") (pintype "passive"))
      (node (ref "R119") (pin "1") (pinfunction "1_1") (pintype "passive"))
    )
    (net (code "43") (name "Net-(IC101-S1)") (class "Default")
      (node (ref "C126") (pin "2") (pinfunction "2_2") (pintype "passive"))
      (node (ref "IC101") (pin "4") (pinfunction "S1_4") (pintype "passive"))
      (node (ref "R144") (pin "1") (pinfunction "1_1") (pintype "passive"))
    )
    (net (code "44") (name "Net-(IC101-S2)") (class "Default")
      (node (ref "C127") (pin "2") (pinfunction "2_2") (pintype "passive"))
      (node (ref "IC101") (pin "5") (pinfunction "S2_5") (pintype "passive"))
      (node (ref "R145") (pin "1") (pinfunction "1_1") (pintype "passive"))
    )
    (net (code "45") (name "Net-(IC101-S3)") (class "Default")
      (node (ref "C128") (pin "2") (pinfunction "2_2") (pintype "passive"))
      (node (ref "IC101") (pin "6") (pinfunction "S3_6") (pintype "passive"))
      (node (ref "R146") (pin "1") (pinfunction "1_1") (pintype "passive"))
    )
    (net (code "46") (name "Net-(IC101-S4)") (class "Default")
      (node (ref "C129") (pin "2") (pinfunction "2_2") (pintype "passive"))
      (node (ref "IC101") (pin "7") (pinfunction "S4_7") (pintype "passive"))
      (node (ref "R147") (pin "1") (pinfunction "1_1") (pintype "passive"))
    )
    (net (code "47") (name "Net-(IC101-S5)") (class "Default")
      (node (ref "C130") (pin "2") (pinfunction "2_2") (pintype "passive"))
      (node (ref "IC101") (pin "12") (pinfunction "S5_12") (pintype "passive"))
      (node (ref "R148") (pin "1") (pinfunction "1_1") (pintype "passive"))
    )
    (net (code "48") (name "Net-(IC101-S6)") (class "Default")
      (node (ref "C131") (pin "2") (pinfunction "2_2") (pintype "passive"))
      (node (ref "IC101") (pin "11") (pinfunction "S6_11") (pintype "passive"))
      (node (ref "R149") (pin "1") (pinfunction "1_1") (pintype "passive"))
    )
    (net (code "49") (name "Net-(IC101-S7)") (class "Default")
      (node (ref "C132") (pin "2") (pinfunction "2_2") (pintype "passive"))
      (node (ref "IC101") (pin "10") (pinfunction "S7_10") (pintype "passive"))
      (node (ref "R150") (pin "1") (pinfunction "1_1") (pintype "passive"))
    )
    (net (code "50") (name "Net-(IC101-S8)") (class "Default")
      (node (ref "C133") (pin "2") (pinfunction "2_2") (pintype "passive"))
      (node (ref "IC101") (pin "9") (pinfunction "S8_9") (pintype "passive"))
      (node (ref "R151") (pin "1") (pinfunction "1_1") (pintype "passive"))
    )
    (net (code "51") (name "Net-(IC104-S1)") (class "Default")
      (node (ref "C117") (pin "2") (pinfunction "2_2") (pintype "passive"))
      (node (ref "IC104") (pin "4") (pinfunction "S1_4") (pintype "passive"))
      (node (ref "R128") (pin "1") (pinfunction "1_1") (pintype "passive"))
    )
    (net (code "52") (name "Net-(IC104-S2)") (class "Default")
      (node (ref "C118") (pin "2") (pinfunction "2_2") (pintype "passive"))
      (node (ref "IC104") (pin "5") (pinfunction "S2_5") (pintype "passive"))
      (node (ref "R129") (pin "1") (pinfunction "1_1") (pintype "passive"))
    )
    (net (code "53") (name "Net-(IC104-S3)") (class "Default")
      (node (ref "C119") (pin "2") (pinfunction "2_2") (pintype "passive"))
      (node (ref "IC104") (pin "6") (pinfunction "S3_6") (pintype "passive"))
      (node (ref "R130") (pin "1") (pinfunction "1_1") (pintype "passive"))
    )
    (net (code "54") (name "Net-(IC104-S4)") (class "Default")
      (node (ref "C120") (pin "2") (pinfunction "2_2") (pintype "passive"))
      (node (ref "IC104") (pin "7") (pinfunction "S4_7") (pintype "passive"))
      (node (ref "R131") (pin "1") (pinfunction "1_1") (pintype "passive"))
    )
    (net (code "55") (name "Net-(IC104-S5)") (class "Default")
      (node (ref "C121") (pin "2") (pinfunction "2_2") (pintype "passive"))
      (node (ref "IC104") (pin "12") (pinfunction "S5_12") (pintype "passive"))
      (node (ref "R132") (pin "1") (pinfunction "1_1") (pintype "passive"))
    )
    (net (code "56") (name "Net-(IC104-S6)") (class "Default")
      (node (ref "C122") (pin "2") (pinfunction "2_2") (pintype "passive"))
      (node (ref "IC104") (pin "11") (pinfunction "S6_11") (pintype "passive"))
      (node (ref "R133") (pin "1") (pinfunction "1_1") (pintype "passive"))
    )
    (net (code "57") (name "Net-(IC104-S7)") (class "Default")
      (node (ref "C123") (pin "2") (pinfunction "2_2") (pintype "passive"))
      (node (ref "IC104") (pin "10") (pinfunction "S7_10") (pintype "passive"))
      (node (ref "R134") (pin "1") (pinfunction "1_1") (pintype "passive"))
    )
    (net (code "58") (name "Net-(IC104-S8)") (class "Default")
      (node (ref "C124") (pin "2") (pinfunction "2_2") (pintype "passive"))
      (node (ref "IC104") (pin "9") (pinfunction "S8_9") (pintype "passive"))
      (node (ref "R135") (pin "1") (pinfunction "1_1") (pintype "passive"))
    )
    (net (code "59") (name "Net-(U100--IN)") (class "Default")
      (node (ref "R108") (pin "1") (pinfunction "1_1") (pintype "passive"))
      (node (ref "U100") (pin "1") (pinfunction "OUT_1") (pintype "output"))
      (node (ref "U100") (pin "4") (pinfunction "-IN_4") (pintype "input"))
    )
    (net (code "60") (name "Net-(U101--IN)") (class "Default")
      (node (ref "R109") (pin "1") (pinfunction "1_1") (pintype "passive"))
      (node (ref "U101") (pin "1") (pinfunction "OUT_1") (pintype "output"))
      (node (ref "U101") (pin "4") (pinfunction "-IN_4") (pintype "input"))
    )
  )
)
